# EasyEda_Schematics_Format_of_Bussiness_c.net
KiCad netlist of a schematic drawn in EasyEDA
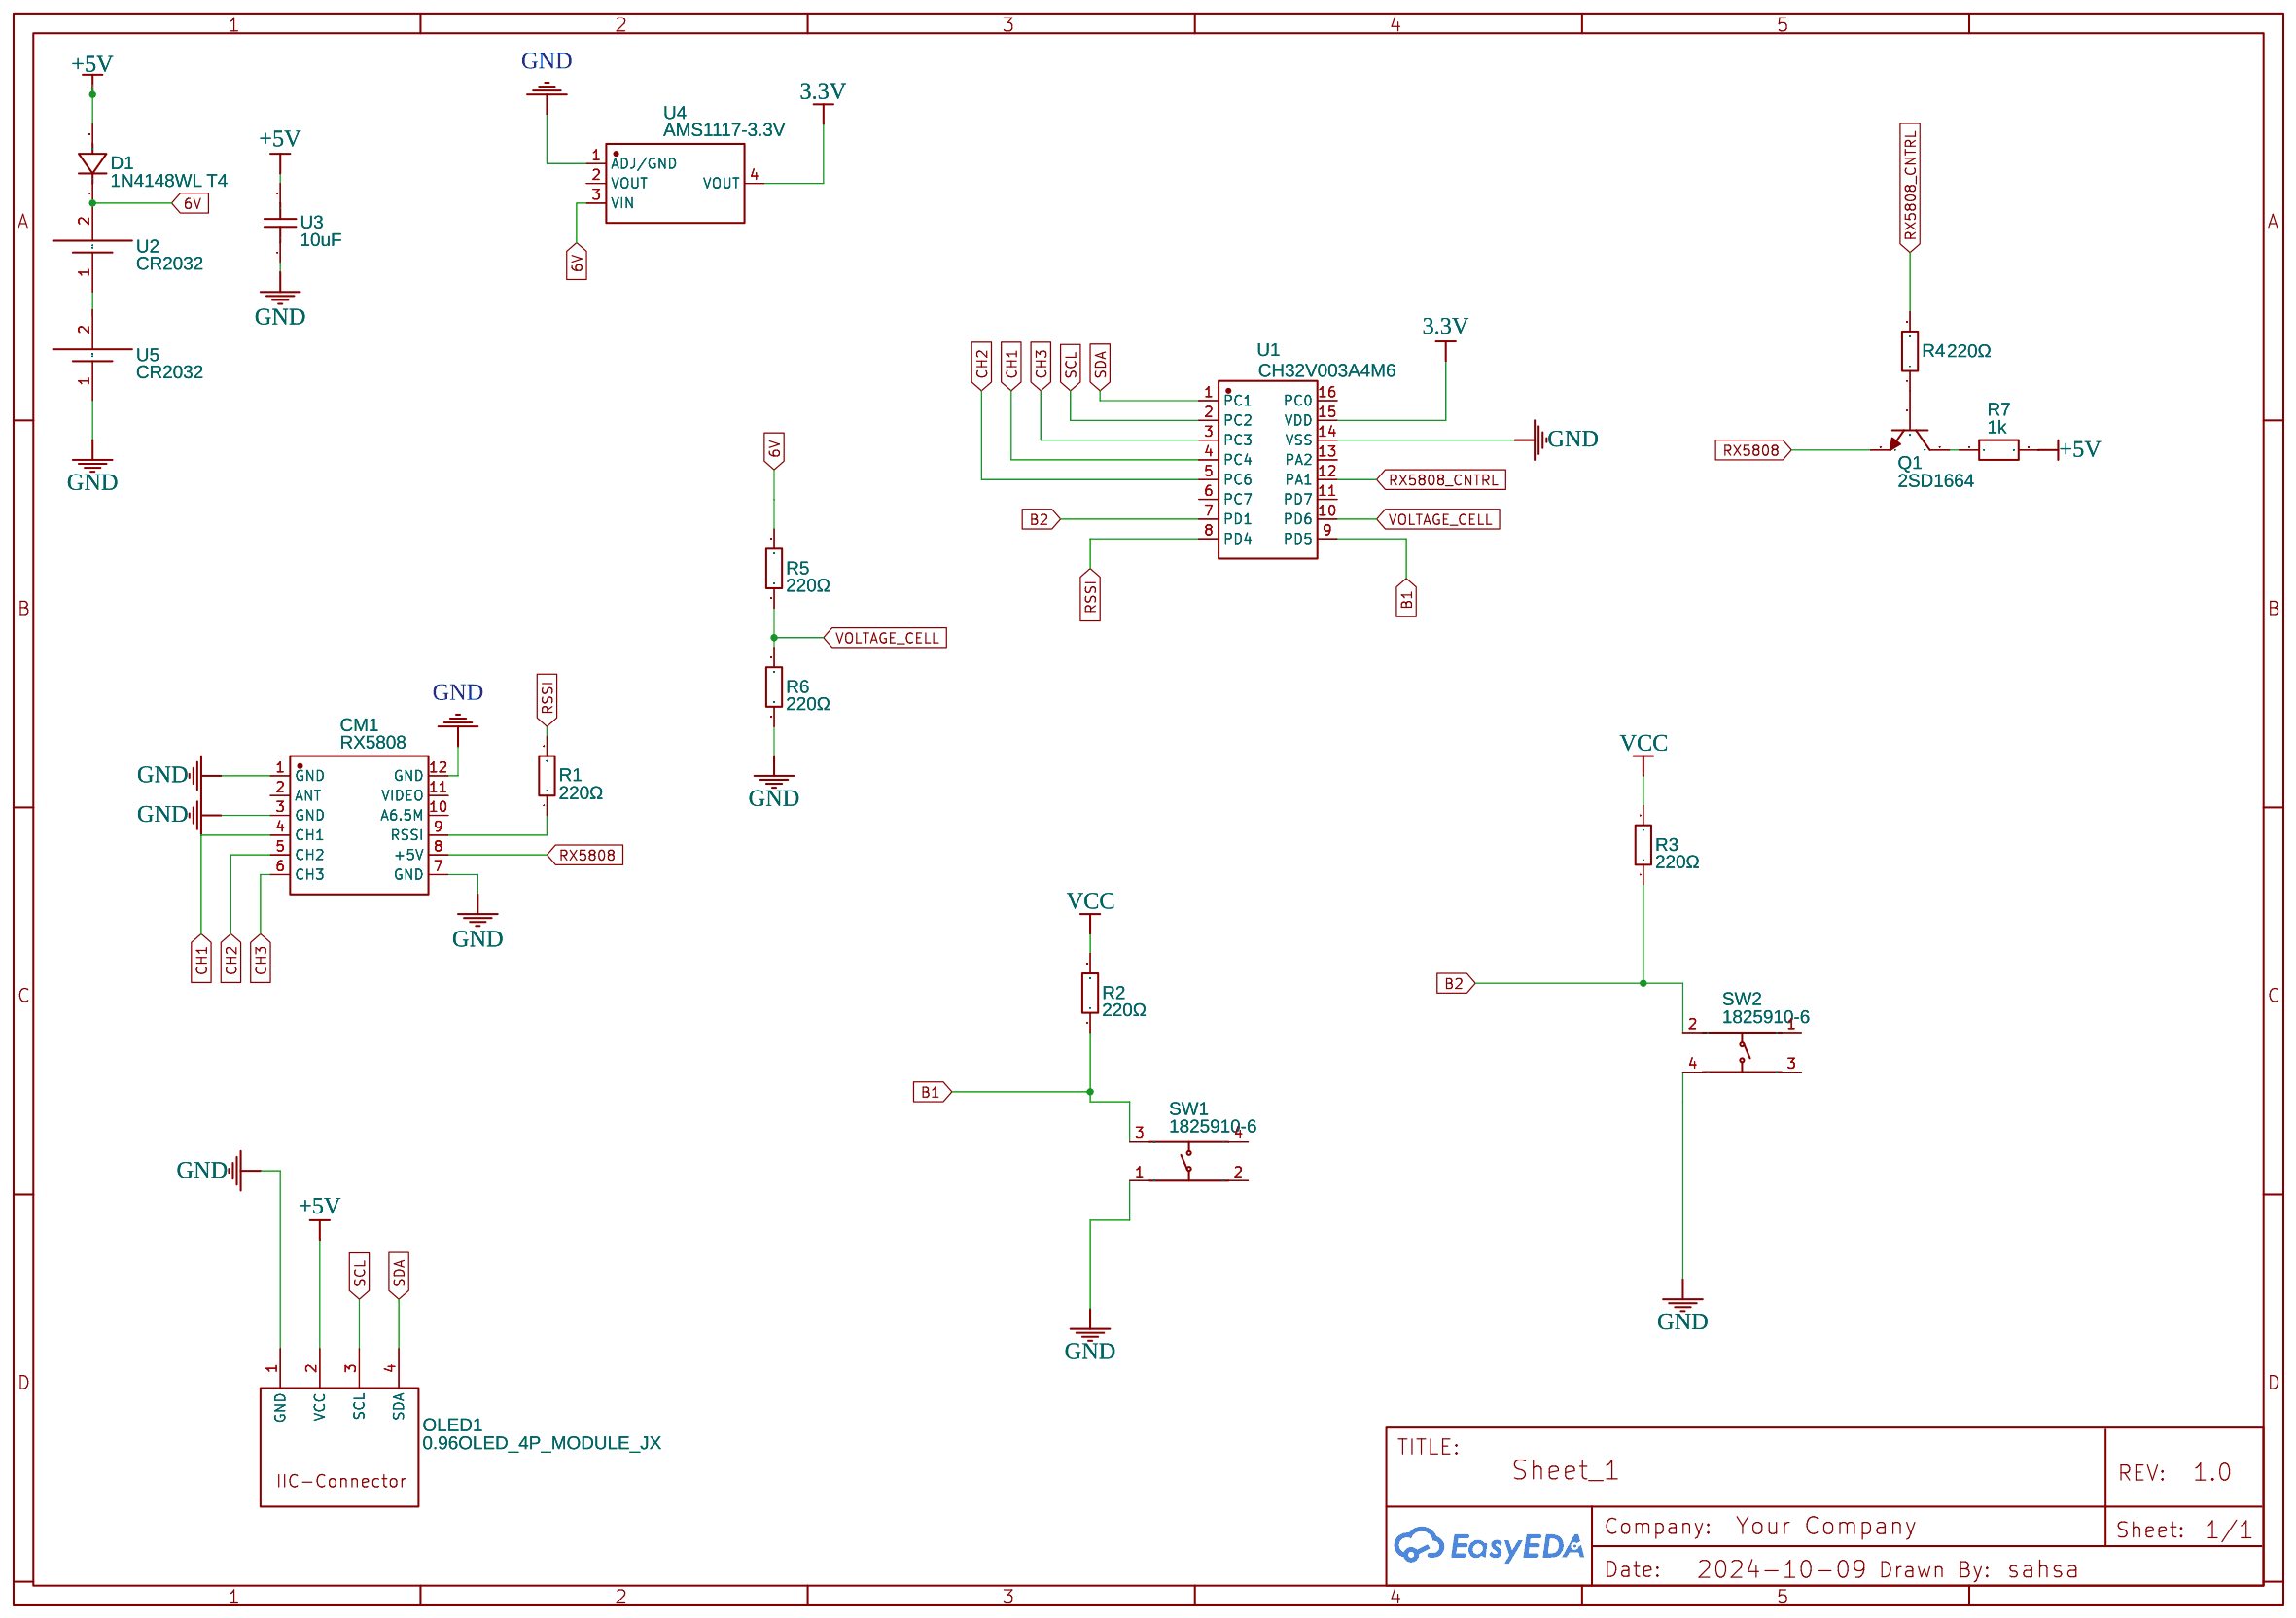
[diagram p0: schematic sheet]

(export (version "E")
  (design (tool "Eeschema 10.0.6"))
  (components
    (comp (ref "CM1") (value "RX5808") (libsource (lib "") (part "RX5808")))
    (comp (ref "D1")
      (value "1N4148WL T4")
      (fields (field (name "Manufacturer") "晶导微电子"))
      (libsource (lib "") (part "1N4148WL T4"))
    )
    (comp (ref "OLED1") (value "0.96OLED_4P_MODULE_JX") (libsource (lib "") (part "0.96OLED_4P_MODULE_JX")))
    (comp (ref "Q1")
      (value "2SD1664")
      (fields (field (name "Manufacturer") "Hottech(合科泰)"))
      (libsource (lib "") (part "2SD1664"))
    )
    (comp (ref "R1")
      (value "220Ω")
      (fields
        (field (name "Manufacturer Part") "QR1206J220RP05Z")
        (field (name "Manufacturer") "EVER OHMS(天二科技)")
      )
      (libsource (lib "") (part "QR1206J220RP05"))
    )
    (comp (ref "R2")
      (value "220Ω")
      (fields
        (field (name "Manufacturer Part") "QR1206J220RP05Z")
        (field (name "Manufacturer") "EVER OHMS(天二科技)")
      )
      (libsource (lib "") (part "QR1206J220RP05"))
    )
    (comp (ref "R3")
      (value "220Ω")
      (fields
        (field (name "Manufacturer Part") "QR1206J220RP05Z")
        (field (name "Manufacturer") "EVER OHMS(天二科技)")
      )
      (libsource (lib "") (part "QR1206J220RP05"))
    )
    (comp (ref "R4")
      (value "220Ω")
      (fields (field (name "Manufacturer Part") "RC1206FR-07220RL") (field (name "Manufacturer") "YAGEO(国巨)"))
      (libsource (lib "") (part "RC1206FR-07220RL"))
    )
    (comp (ref "R5")
      (value "220Ω")
      (fields (field (name "Manufacturer Part") "RC1206FR-07220RL") (field (name "Manufacturer") "YAGEO(国巨)"))
      (libsource (lib "") (part "RC1206FR-07220RL"))
    )
    (comp (ref "R6")
      (value "220Ω")
      (fields (field (name "Manufacturer Part") "RC1206FR-07220RL") (field (name "Manufacturer") "YAGEO(国巨)"))
      (libsource (lib "") (part "RC1206FR-07220RL"))
    )
    (comp (ref "R7") (value "1k") (libsource (lib "") (part "R_1206_EU")))
    (comp (ref "SW1")
      (value "1825910-6")
      (fields (field (name "Manufacturer") "TE Connectivity(泰科电子)"))
      (libsource (lib "") (part "1825910-6"))
    )
    (comp (ref "SW2")
      (value "1825910-6")
      (fields (field (name "Manufacturer") "TE Connectivity(泰科电子)"))
      (libsource (lib "") (part "1825910-6_1"))
    )
    (comp (ref "U1")
      (value "CH32V003A4M6")
      (fields (field (name "Manufacturer") "WCH(南京沁恒)"))
      (libsource (lib "") (part "CH32V003A4M6"))
    )
    (comp (ref "U2") (value "CR2032") (libsource (lib "") (part "CR2032")))
    (comp (ref "U3")
      (value "10uF")
      (fields
        (field (name "Manufacturer Part") "TCC1206X5R106K500HT")
        (field (name "Manufacturer") "CCTC(三环)")
      )
      (libsource (lib "") (part "TCC1206X5R106K500HT"))
    )
    (comp (ref "U4")
      (value "AMS1117-3.3V")
      (fields (field (name "Manufacturer") "WPMtek(维攀)"))
      (libsource (lib "") (part "AMS1117-3.3V"))
    )
    (comp (ref "U5") (value "CR2032") (libsource (lib "") (part "CR2032")))
  )
  (nets
    (net (code "1") (name "+5V") (class "Default")
      (node (ref "D1") (pin "2") (pinfunction "A_2") (pintype "unspecified"))
      (node (ref "OLED1") (pin "2") (pinfunction "VCC_2") (pintype "unspecified"))
      (node (ref "R7") (pin "2") (pinfunction "2_2") (pintype "unspecified"))
      (node (ref "U3") (pin "2") (pinfunction "2_2") (pintype "unspecified"))
    )
    (net (code "2") (name "3.3V") (class "Default")
      (node (ref "U1") (pin "15") (pinfunction "VDD_15") (pintype "unspecified"))
      (node (ref "U4") (pin "4") (pinfunction "VOUT_4") (pintype "unspecified"))
    )
    (net (code "3") (name "6V") (class "Default")
      (node (ref "D1") (pin "1") (pinfunction "K_1") (pintype "unspecified"))
      (node (ref "R5") (pin "2") (pinfunction "2_2") (pintype "input"))
      (node (ref "U2") (pin "2") (pinfunction "2_2") (pintype "unspecified"))
      (node (ref "U4") (pin "3") (pinfunction "VIN_3") (pintype "unspecified"))
    )
    (net (code "4") (name "B1") (class "Default")
      (node (ref "R2") (pin "1") (pinfunction "1_1") (pintype "unspecified"))
      (node (ref "SW1") (pin "3") (pinfunction "3_3") (pintype "unspecified"))
      (node (ref "U1") (pin "9") (pinfunction "PD5_9") (pintype "unspecified"))
    )
    (net (code "5") (name "B2") (class "Default")
      (node (ref "R3") (pin "1") (pinfunction "1_1") (pintype "unspecified"))
      (node (ref "SW2") (pin "2") (pinfunction "2_2") (pintype "unspecified"))
      (node (ref "U1") (pin "7") (pinfunction "PD1_7") (pintype "unspecified"))
    )
    (net (code "6") (name "CH1") (class "Default")
      (node (ref "CM1") (pin "4") (pinfunction "CH1_4") (pintype "unspecified"))
      (node (ref "U1") (pin "4") (pinfunction "PC4_4") (pintype "unspecified"))
    )
    (net (code "7") (name "CH2") (class "Default")
      (node (ref "CM1") (pin "5") (pinfunction "CH2_5") (pintype "unspecified"))
      (node (ref "U1") (pin "5") (pinfunction "PC6_5") (pintype "unspecified"))
    )
    (net (code "8") (name "CH3") (class "Default")
      (node (ref "CM1") (pin "6") (pinfunction "CH3_6") (pintype "unspecified"))
      (node (ref "U1") (pin "3") (pinfunction "PC3_3") (pintype "unspecified"))
    )
    (net (code "9") (name "GND") (class "Default")
      (node (ref "CM1") (pin "1") (pinfunction "GND_1") (pintype "unspecified"))
      (node (ref "CM1") (pin "12") (pinfunction "GND_12") (pintype "unspecified"))
      (node (ref "CM1") (pin "3") (pinfunction "GND_3") (pintype "unspecified"))
      (node (ref "CM1") (pin "7") (pinfunction "GND_7") (pintype "unspecified"))
      (node (ref "OLED1") (pin "1") (pinfunction "GND_1") (pintype "unspecified"))
      (node (ref "R6") (pin "1") (pinfunction "1_1") (pintype "input"))
      (node (ref "SW1") (pin "1") (pinfunction "1_1") (pintype "unspecified"))
      (node (ref "SW2") (pin "4") (pinfunction "4_4") (pintype "unspecified"))
      (node (ref "U1") (pin "14") (pinfunction "VSS_14") (pintype "unspecified"))
      (node (ref "U3") (pin "1") (pinfunction "1_1") (pintype "unspecified"))
      (node (ref "U4") (pin "1") (pinfunction "ADJ/GND_1") (pintype "unspecified"))
      (node (ref "U5") (pin "1") (pinfunction "1_1") (pintype "unspecified"))
    )
    (net (code "10") (name "Net-(CM1-RSSI)") (class "Default")
      (node (ref "CM1") (pin "9") (pinfunction "RSSI_9") (pintype "unspecified"))
      (node (ref "R1") (pin "1") (pinfunction "1_1") (pintype "unspecified"))
    )
    (net (code "11") (name "Net-(Q1-B)") (class "Default")
      (node (ref "Q1") (pin "1") (pinfunction "B_1") (pintype "unspecified"))
      (node (ref "R4") (pin "1") (pinfunction "1_1") (pintype "input"))
    )
    (net (code "12") (name "Net-(Q1-C)") (class "Default")
      (node (ref "Q1") (pin "2") (pinfunction "C_2") (pintype "unspecified"))
      (node (ref "R7") (pin "1") (pinfunction "1_1") (pintype "unspecified"))
    )
    (net (code "13") (name "Net-(U2-Pad1)") (class "Default")
      (node (ref "U2") (pin "1") (pinfunction "1_1") (pintype "unspecified"))
      (node (ref "U5") (pin "2") (pinfunction "2_2") (pintype "unspecified"))
    )
    (net (code "14") (name "RSSI") (class "Default")
      (node (ref "R1") (pin "2") (pinfunction "2_2") (pintype "unspecified"))
      (node (ref "U1") (pin "8") (pinfunction "PD4_8") (pintype "unspecified"))
    )
    (net (code "15") (name "RX5808") (class "Default")
      (node (ref "CM1") (pin "8") (pinfunction "+5V_8") (pintype "unspecified"))
      (node (ref "Q1") (pin "3") (pinfunction "E_3") (pintype "unspecified"))
    )
    (net (code "16") (name "RX5808_CNTRL") (class "Default")
      (node (ref "R4") (pin "2") (pinfunction "2_2") (pintype "input"))
      (node (ref "U1") (pin "12") (pinfunction "PA1_12") (pintype "unspecified"))
    )
    (net (code "17") (name "SCL") (class "Default")
      (node (ref "OLED1") (pin "3") (pinfunction "SCL_3") (pintype "unspecified"))
      (node (ref "U1") (pin "2") (pinfunction "PC2_2") (pintype "unspecified"))
    )
    (net (code "18") (name "SDA") (class "Default")
      (node (ref "OLED1") (pin "4") (pinfunction "SDA_4") (pintype "unspecified"))
      (node (ref "U1") (pin "1") (pinfunction "PC1_1") (pintype "unspecified"))
    )
    (net (code "19") (name "VCC") (class "Default")
      (node (ref "R2") (pin "2") (pinfunction "2_2") (pintype "unspecified"))
      (node (ref "R3") (pin "2") (pinfunction "2_2") (pintype "unspecified"))
    )
    (net (code "20") (name "VOLTAGE_CELL") (class "Default")
      (node (ref "R5") (pin "1") (pinfunction "1_1") (pintype "input"))
      (node (ref "R6") (pin "2") (pinfunction "2_2") (pintype "input"))
      (node (ref "U1") (pin "10") (pinfunction "PD6_10") (pintype "unspecified"))
    )
    (net (code "21") (name "unconnected-(CM1-A6.5M-Pad10)") (class "Default")
      (node (ref "CM1") (pin "10") (pinfunction "A6.5M_10") (pintype "unspecified"))
    )
    (net (code "22") (name "unconnected-(CM1-ANT-Pad2)") (class "Default")
      (node (ref "CM1") (pin "2") (pinfunction "ANT_2") (pintype "unspecified"))
    )
    (net (code "23") (name "unconnected-(CM1-VIDEO-Pad11)") (class "Default")
      (node (ref "CM1") (pin "11") (pinfunction "VIDEO_11") (pintype "unspecified"))
    )
    (net (code "24") (name "unconnected-(SW1-Pad2)") (class "Default")
      (node (ref "SW1") (pin "2") (pinfunction "2_2") (pintype "unspecified"))
    )
    (net (code "25") (name "unconnected-(SW1-Pad4)") (class "Default")
      (node (ref "SW1") (pin "4") (pinfunction "4_4") (pintype "unspecified"))
    )
    (net (code "26") (name "unconnected-(SW2-Pad1)") (class "Default")
      (node (ref "SW2") (pin "1") (pinfunction "1_1") (pintype "unspecified"))
    )
    (net (code "27") (name "unconnected-(SW2-Pad3)") (class "Default")
      (node (ref "SW2") (pin "3") (pinfunction "3_3") (pintype "unspecified"))
    )
    (net (code "28") (name "unconnected-(U1-PA2-Pad13)") (class "Default")
      (node (ref "U1") (pin "13") (pinfunction "PA2_13") (pintype "unspecified"))
    )
    (net (code "29") (name "unconnected-(U1-PC0-Pad16)") (class "Default")
      (node (ref "U1") (pin "16") (pinfunction "PC0_16") (pintype "unspecified"))
    )
    (net (code "30") (name "unconnected-(U1-PC7-Pad6)") (class "Default")
      (node (ref "U1") (pin "6") (pinfunction "PC7_6") (pintype "unspecified"))
    )
    (net (code "31") (name "unconnected-(U1-PD7-Pad11)") (class "Default")
      (node (ref "U1") (pin "11") (pinfunction "PD7_11") (pintype "unspecified"))
    )
    (net (code "32") (name "unconnected-(U4-VOUT-Pad2)") (class "Default")
      (node (ref "U4") (pin "2") (pinfunction "VOUT_2") (pintype "unspecified"))
    )
  )
)
